# NHD-C12832A1Z_Breakout_rev2.net
KiCad netlist of a schematic drawn in EAGLE
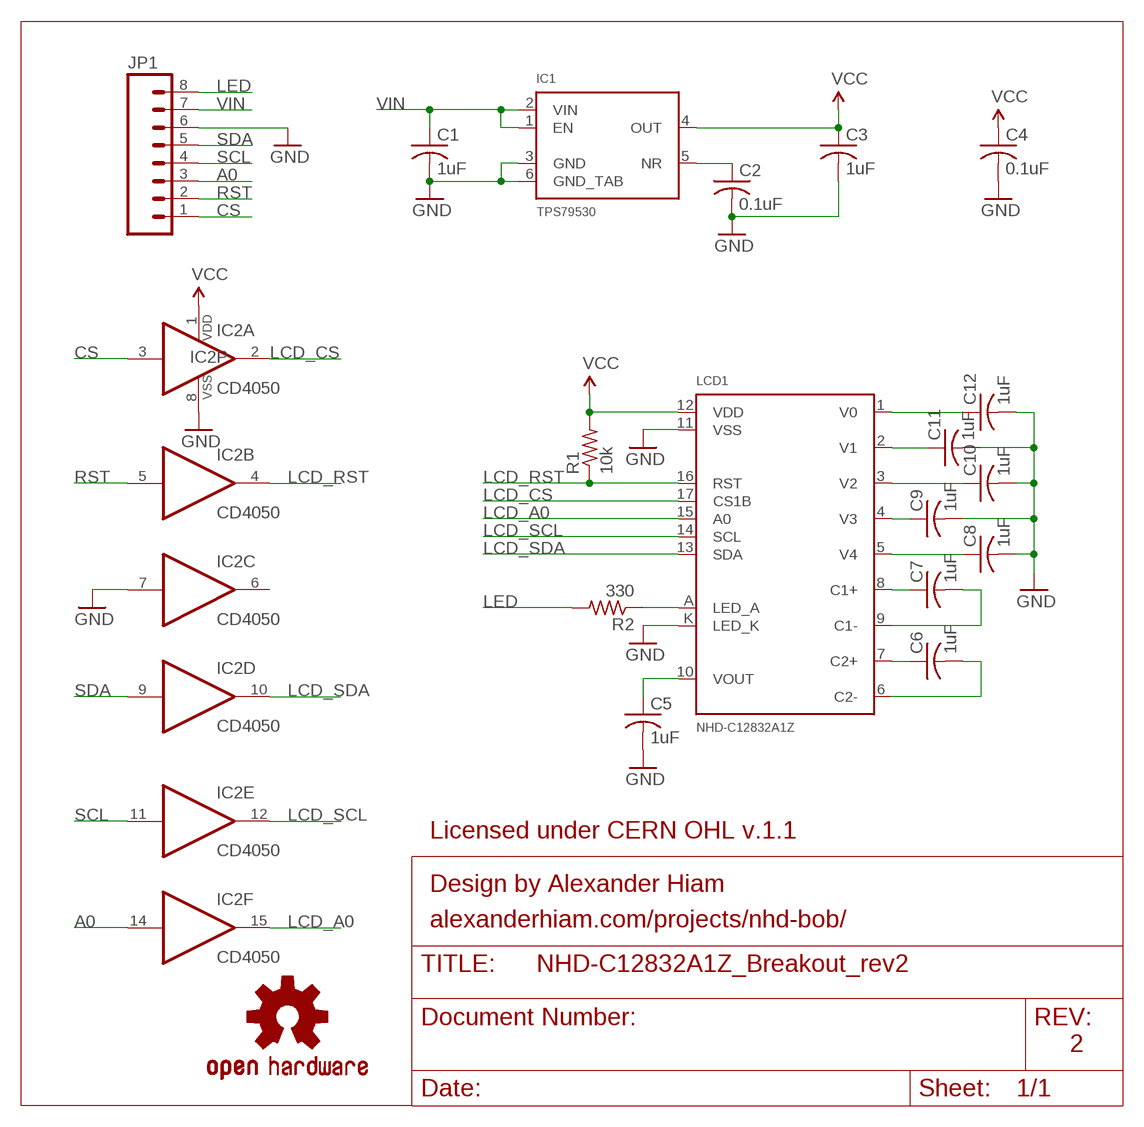
[diagram p0: schematic, sheet 1]

(export (version "E")
  (design (tool "Eeschema 10.0.6"))
  (components
    (comp (ref "C1")
      (value "1uF")
      (footprint "eagle-import:C0603")
      (libsource (lib "eagle-import") (part "C-USC0603"))
    )
    (comp (ref "C2")
      (value "0.1uF")
      (footprint "eagle-import:C0603")
      (libsource (lib "eagle-import") (part "C-USC0603"))
    )
    (comp (ref "C3")
      (value "1uF")
      (footprint "eagle-import:C0603")
      (libsource (lib "eagle-import") (part "C-USC0603"))
    )
    (comp (ref "C4")
      (value "0.1uF")
      (footprint "eagle-import:C0603")
      (libsource (lib "eagle-import") (part "C-USC0603"))
    )
    (comp (ref "C5")
      (value "1uF")
      (footprint "eagle-import:C0603")
      (libsource (lib "eagle-import") (part "C-USC0603"))
    )
    (comp (ref "C6")
      (value "1uF")
      (footprint "eagle-import:C0603")
      (libsource (lib "eagle-import") (part "C-USC0603"))
    )
    (comp (ref "C7")
      (value "1uF")
      (footprint "eagle-import:C0603")
      (libsource (lib "eagle-import") (part "C-USC0603"))
    )
    (comp (ref "C8")
      (value "1uF")
      (footprint "eagle-import:C0603")
      (libsource (lib "eagle-import") (part "C-USC0603"))
    )
    (comp (ref "C9")
      (value "1uF")
      (footprint "eagle-import:C0603")
      (libsource (lib "eagle-import") (part "C-USC0603"))
    )
    (comp (ref "C10")
      (value "1uF")
      (footprint "eagle-import:C0603")
      (libsource (lib "eagle-import") (part "C-USC0603"))
    )
    (comp (ref "C11")
      (value "1uF")
      (footprint "eagle-import:C0603")
      (libsource (lib "eagle-import") (part "C-USC0603"))
    )
    (comp (ref "C12")
      (value "1uF")
      (footprint "eagle-import:C0603")
      (libsource (lib "eagle-import") (part "C-USC0603"))
    )
    (comp (ref "IC1")
      (value "TPS79530")
      (footprint "eagle-import:SOT223-6")
      (libsource (lib "eagle-import") (part "TPS795XX"))
    )
    (comp (ref "IC2")
      (value "CD4050")
      (footprint "eagle-import:SO16")
      (libsource (lib "eagle-import") (part "4050D"))
    )
    (comp (ref "JP1")
      (value "M081X08")
      (footprint "eagle-import:1X08")
      (libsource (lib "eagle-import") (part "M081X08"))
    )
    (comp (ref "LCD1")
      (value "NHD-C12832A1Z")
      (footprint "eagle-import:NHD-C12832A1Z")
      (libsource (lib "eagle-import") (part "NHD-C12832A1Z"))
    )
    (comp (ref "R1")
      (value "10k")
      (footprint "eagle-import:R0603")
      (libsource (lib "eagle-import") (part "R-US_R0603"))
    )
    (comp (ref "R2")
      (value "330")
      (footprint "eagle-import:R0603")
      (libsource (lib "eagle-import") (part "R-US_R0603"))
    )
    (comp (ref "U$1")
      (value "OSHW-LOGOS")
      (footprint "eagle-import:OSHW-LOGO-S")
      (libsource (lib "eagle-import") (part "OSHW-LOGOS"))
    )
    (comp (ref "U$2")
      (value "CERN_V1.1_LG")
      (footprint "eagle-import:CERN_V1.1_LG")
      (libsource (lib "eagle-import") (part "CERN_V1.1_LG"))
    )
  )
  (nets
    (net (code "1") (name "/A0") (class "Default")
      (node (ref "IC2") (pin "14") (pinfunction "I_14") (pintype "input"))
      (node (ref "JP1") (pin "3") (pinfunction "3_3") (pintype "passive"))
    )
    (net (code "2") (name "/CS") (class "Default")
      (node (ref "IC2") (pin "3") (pinfunction "I_3") (pintype "input"))
      (node (ref "JP1") (pin "1") (pinfunction "1_1") (pintype "passive"))
    )
    (net (code "3") (name "/LCD_A0") (class "Default")
      (node (ref "IC2") (pin "15") (pinfunction "O_15") (pintype "output"))
      (node (ref "LCD1") (pin "15") (pinfunction "A0_15") (pintype "bidirectional"))
    )
    (net (code "4") (name "/LCD_CS") (class "Default")
      (node (ref "IC2") (pin "2") (pinfunction "O_2") (pintype "output"))
      (node (ref "LCD1") (pin "17") (pinfunction "CS1B_17") (pintype "bidirectional"))
    )
    (net (code "5") (name "/LCD_RST") (class "Default")
      (node (ref "IC2") (pin "4") (pinfunction "O_4") (pintype "output"))
      (node (ref "LCD1") (pin "16") (pinfunction "RST_16") (pintype "bidirectional"))
      (node (ref "R1") (pin "1") (pinfunction "1_1") (pintype "passive"))
    )
    (net (code "6") (name "/LCD_SCL") (class "Default")
      (node (ref "IC2") (pin "12") (pinfunction "O_12") (pintype "output"))
      (node (ref "LCD1") (pin "14") (pinfunction "SCL_14") (pintype "bidirectional"))
    )
    (net (code "7") (name "/LCD_SDA") (class "Default")
      (node (ref "IC2") (pin "10") (pinfunction "O_10") (pintype "output"))
      (node (ref "LCD1") (pin "13") (pinfunction "SDA_13") (pintype "bidirectional"))
    )
    (net (code "8") (name "/LED") (class "Default")
      (node (ref "JP1") (pin "8") (pinfunction "8_8") (pintype "passive"))
      (node (ref "R2") (pin "2") (pinfunction "2_2") (pintype "passive"))
    )
    (net (code "9") (name "/RST") (class "Default")
      (node (ref "IC2") (pin "5") (pinfunction "I_5") (pintype "input"))
      (node (ref "JP1") (pin "2") (pinfunction "2_2") (pintype "passive"))
    )
    (net (code "10") (name "/SCL") (class "Default")
      (node (ref "IC2") (pin "11") (pinfunction "I_11") (pintype "input"))
      (node (ref "JP1") (pin "4") (pinfunction "4_4") (pintype "passive"))
    )
    (net (code "11") (name "/SDA") (class "Default")
      (node (ref "IC2") (pin "9") (pinfunction "I_9") (pintype "input"))
      (node (ref "JP1") (pin "5") (pinfunction "5_5") (pintype "passive"))
    )
    (net (code "12") (name "/VIN") (class "Default")
      (node (ref "C1") (pin "1") (pinfunction "1_1") (pintype "passive"))
      (node (ref "IC1") (pin "1") (pinfunction "EN_1") (pintype "bidirectional"))
      (node (ref "IC1") (pin "2") (pinfunction "VIN_2") (pintype "bidirectional"))
      (node (ref "JP1") (pin "7") (pinfunction "7_7") (pintype "passive"))
    )
    (net (code "13") (name "GND") (class "Default")
      (node (ref "C1") (pin "2") (pinfunction "2_2") (pintype "passive"))
      (node (ref "C10") (pin "2") (pinfunction "2_2") (pintype "passive"))
      (node (ref "C11") (pin "2") (pinfunction "2_2") (pintype "passive"))
      (node (ref "C12") (pin "2") (pinfunction "2_2") (pintype "passive"))
      (node (ref "C2") (pin "2") (pinfunction "2_2") (pintype "passive"))
      (node (ref "C3") (pin "2") (pinfunction "2_2") (pintype "passive"))
      (node (ref "C4") (pin "2") (pinfunction "2_2") (pintype "passive"))
      (node (ref "C5") (pin "2") (pinfunction "2_2") (pintype "passive"))
      (node (ref "C8") (pin "2") (pinfunction "2_2") (pintype "passive"))
      (node (ref "C9") (pin "2") (pinfunction "2_2") (pintype "passive"))
      (node (ref "IC1") (pin "3") (pinfunction "GND_3") (pintype "bidirectional"))
      (node (ref "IC1") (pin "6") (pinfunction "GND_TAB_6") (pintype "bidirectional"))
      (node (ref "IC2") (pin "7") (pinfunction "I_7") (pintype "input"))
      (node (ref "IC2") (pin "8") (pinfunction "VSS_8") (pintype "power_in"))
      (node (ref "JP1") (pin "6") (pinfunction "6_6") (pintype "passive"))
      (node (ref "LCD1") (pin "11") (pinfunction "VSS_11") (pintype "bidirectional"))
      (node (ref "LCD1") (pin "K") (pinfunction "LED_K_K") (pintype "bidirectional"))
    )
    (net (code "14") (name "Net-(IC1-NR)") (class "Default")
      (node (ref "C2") (pin "1") (pinfunction "1_1") (pintype "passive"))
      (node (ref "IC1") (pin "5") (pinfunction "NR_5") (pintype "bidirectional"))
    )
    (net (code "15") (name "Net-(LCD1-C1+)") (class "Default")
      (node (ref "C7") (pin "1") (pinfunction "1_1") (pintype "passive"))
      (node (ref "LCD1") (pin "8") (pinfunction "C1+_8") (pintype "bidirectional"))
    )
    (net (code "16") (name "Net-(LCD1-C1-)") (class "Default")
      (node (ref "C7") (pin "2") (pinfunction "2_2") (pintype "passive"))
      (node (ref "LCD1") (pin "9") (pinfunction "C1-_9") (pintype "bidirectional"))
    )
    (net (code "17") (name "Net-(LCD1-C2+)") (class "Default")
      (node (ref "C6") (pin "1") (pinfunction "1_1") (pintype "passive"))
      (node (ref "LCD1") (pin "7") (pinfunction "C2+_7") (pintype "bidirectional"))
    )
    (net (code "18") (name "Net-(LCD1-C2-)") (class "Default")
      (node (ref "C6") (pin "2") (pinfunction "2_2") (pintype "passive"))
      (node (ref "LCD1") (pin "6") (pinfunction "C2-_6") (pintype "bidirectional"))
    )
    (net (code "19") (name "Net-(LCD1-LED_A)") (class "Default")
      (node (ref "LCD1") (pin "A") (pinfunction "LED_A_A") (pintype "bidirectional"))
      (node (ref "R2") (pin "1") (pinfunction "1_1") (pintype "passive"))
    )
    (net (code "20") (name "Net-(LCD1-V0)") (class "Default")
      (node (ref "C12") (pin "1") (pinfunction "1_1") (pintype "passive"))
      (node (ref "LCD1") (pin "1") (pinfunction "V0_1") (pintype "bidirectional"))
    )
    (net (code "21") (name "Net-(LCD1-V1)") (class "Default")
      (node (ref "C11") (pin "1") (pinfunction "1_1") (pintype "passive"))
      (node (ref "LCD1") (pin "2") (pinfunction "V1_2") (pintype "bidirectional"))
    )
    (net (code "22") (name "Net-(LCD1-V2)") (class "Default")
      (node (ref "C10") (pin "1") (pinfunction "1_1") (pintype "passive"))
      (node (ref "LCD1") (pin "3") (pinfunction "V2_3") (pintype "bidirectional"))
    )
    (net (code "23") (name "Net-(LCD1-V3)") (class "Default")
      (node (ref "C9") (pin "1") (pinfunction "1_1") (pintype "passive"))
      (node (ref "LCD1") (pin "4") (pinfunction "V3_4") (pintype "bidirectional"))
    )
    (net (code "24") (name "Net-(LCD1-V4)") (class "Default")
      (node (ref "C8") (pin "1") (pinfunction "1_1") (pintype "passive"))
      (node (ref "LCD1") (pin "5") (pinfunction "V4_5") (pintype "bidirectional"))
    )
    (net (code "25") (name "Net-(LCD1-VOUT)") (class "Default")
      (node (ref "C5") (pin "1") (pinfunction "1_1") (pintype "passive"))
      (node (ref "LCD1") (pin "10") (pinfunction "VOUT_10") (pintype "bidirectional"))
    )
    (net (code "26") (name "VCC") (class "Default")
      (node (ref "C3") (pin "1") (pinfunction "1_1") (pintype "passive"))
      (node (ref "C4") (pin "1") (pinfunction "1_1") (pintype "passive"))
      (node (ref "IC1") (pin "4") (pinfunction "OUT_4") (pintype "bidirectional"))
      (node (ref "IC2") (pin "1") (pinfunction "VDD_1") (pintype "power_in"))
      (node (ref "LCD1") (pin "12") (pinfunction "VDD_12") (pintype "bidirectional"))
      (node (ref "R1") (pin "2") (pinfunction "2_2") (pintype "passive"))
    )
    (net (code "27") (name "unconnected-(IC2C-O-Pad6)") (class "Default")
      (node (ref "IC2") (pin "6") (pinfunction "O_6") (pintype "output"))
    )
  )
)
